# ESenseFE-PreAmpSingalInput.net
KiCad netlist of a schematic drawn in Altium Designer
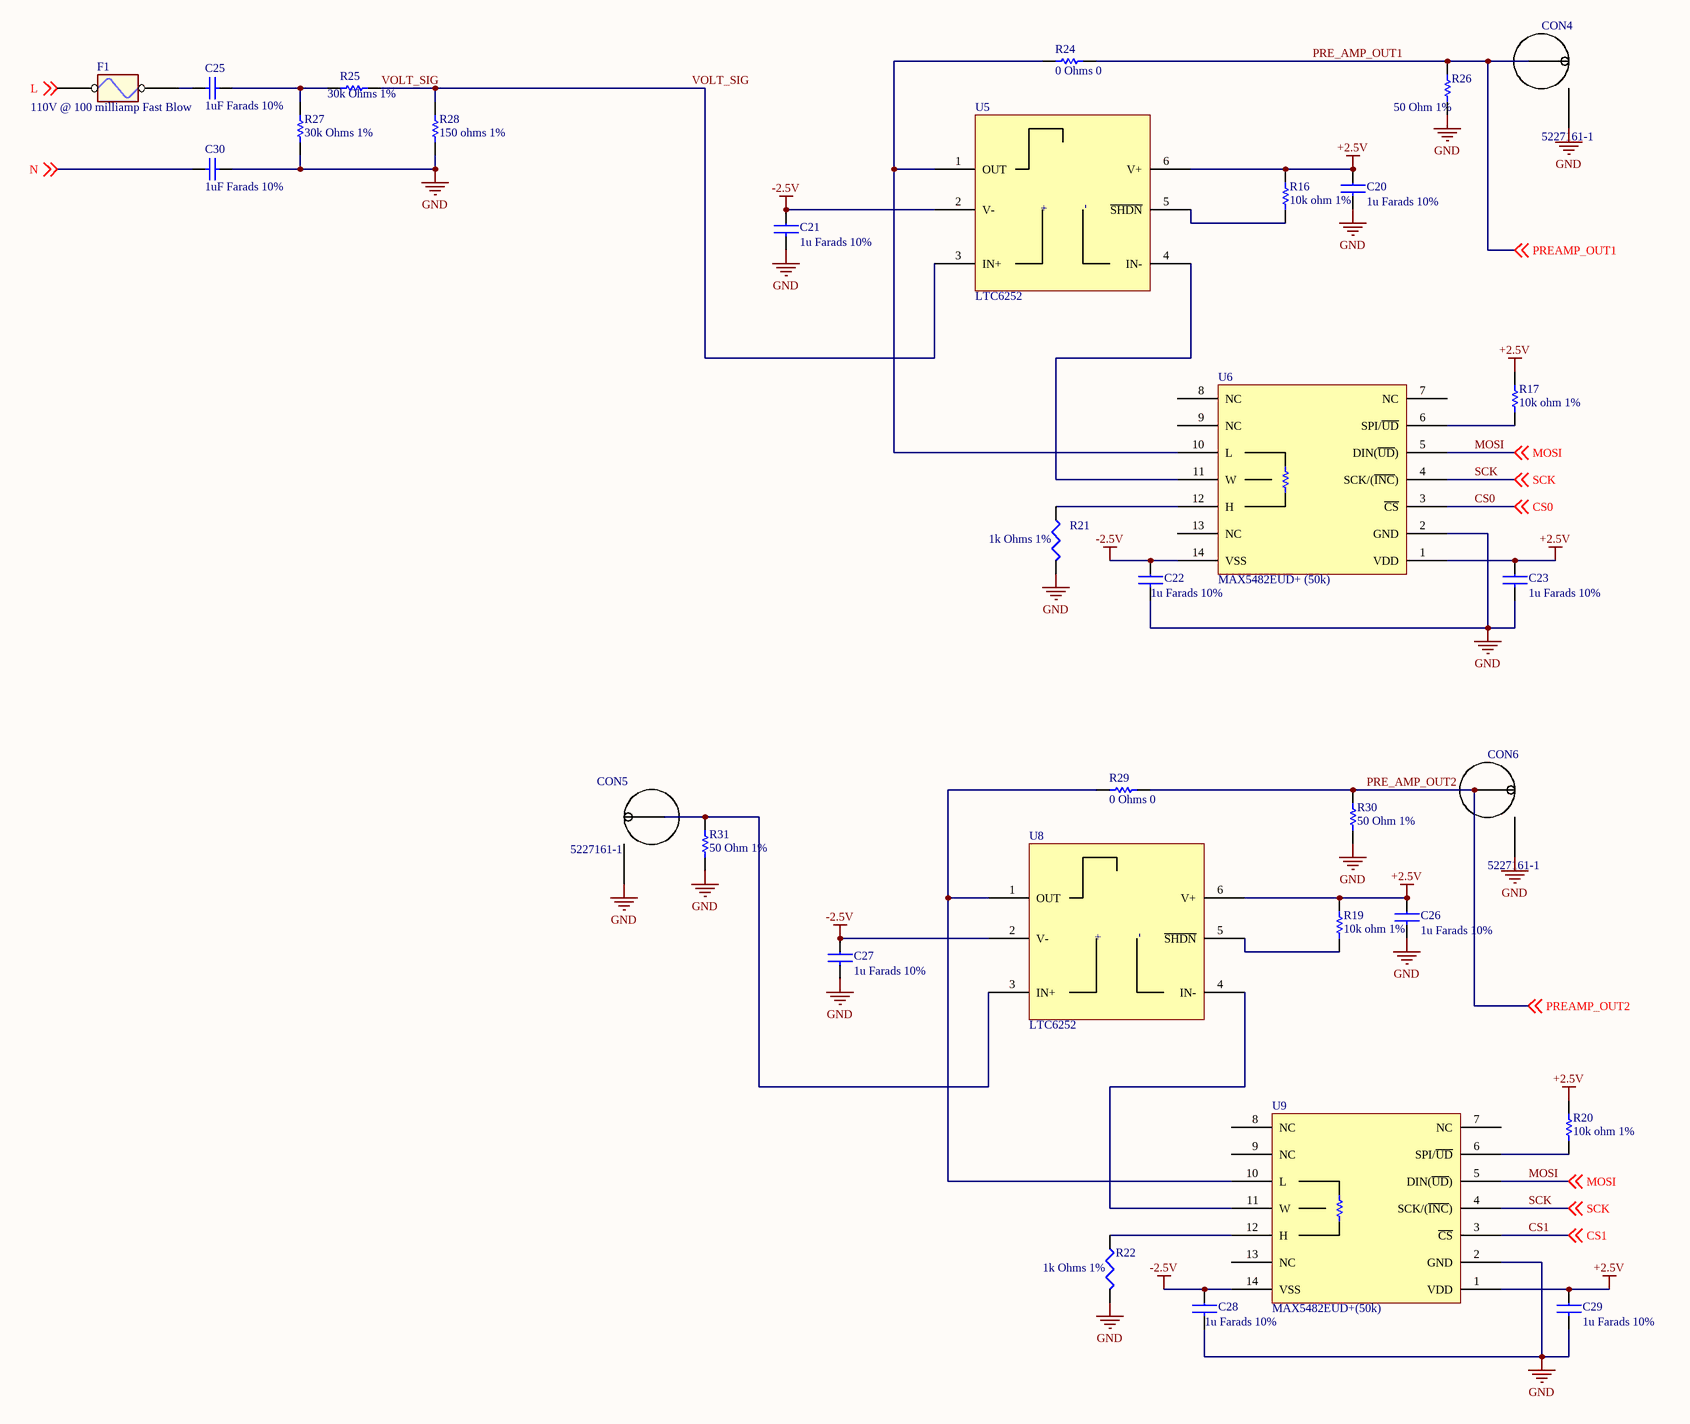
[diagram p0: ESenseFE-PreAmpSingalInput.SchDoc]

(export (version "E")
  (design (tool "Eeschema 10.0.6"))
  (components
    (comp (ref "C20")
      (value "1u Farads 10%")
      (footprint "SM/C_0603")
      (description "CAP CER 1.0UF 10V 10% X5R 0603")
      (fields (field (name "MFRPARTNUM") "GRM188R61A105KA61D"))
      (libsource (lib "FriedParts") (part "CAP NP"))
    )
    (comp (ref "C21")
      (value "1u Farads 10%")
      (footprint "SM/C_0603")
      (description "CAP CER 1.0UF 10V 10% X5R 0603")
      (fields (field (name "MFRPARTNUM") "GRM188R61A105KA61D"))
      (libsource (lib "FriedParts") (part "CAP NP"))
    )
    (comp (ref "C22")
      (value "1u Farads 10%")
      (footprint "SM/C_0603")
      (description "CAP CER 1.0UF 10V 10% X5R 0603")
      (fields (field (name "MFRPARTNUM") "GRM188R61A105KA61D"))
      (libsource (lib "FriedParts") (part "CAP NP"))
    )
    (comp (ref "C23")
      (value "1u Farads 10%")
      (footprint "SM/C_0603")
      (description "CAP CER 1.0UF 10V 10% X5R 0603")
      (fields (field (name "MFRPARTNUM") "GRM188R61A105KA61D"))
      (libsource (lib "FriedParts") (part "CAP NP"))
    )
    (comp (ref "C25")
      (value "1uF Farads 10%")
      (footprint "Y2-Caps-Epocs-1uF-10%")
      (description "Y2 Caps 1uF Epocs")
      (fields (field (name "MFRPARTNUM") "B32026B3105K"))
      (libsource (lib "FriedParts") (part "CAP"))
    )
    (comp (ref "C26")
      (value "1u Farads 10%")
      (footprint "SM/C_0603")
      (description "CAP CER 1.0UF 10V 10% X5R 0603")
      (fields (field (name "MFRPARTNUM") "GRM188R61A105KA61D"))
      (libsource (lib "FriedParts") (part "CAP NP"))
    )
    (comp (ref "C27")
      (value "1u Farads 10%")
      (footprint "SM/C_0603")
      (description "CAP CER 1.0UF 10V 10% X5R 0603")
      (fields (field (name "MFRPARTNUM") "GRM188R61A105KA61D"))
      (libsource (lib "FriedParts") (part "CAP NP"))
    )
    (comp (ref "C28")
      (value "1u Farads 10%")
      (footprint "SM/C_0603")
      (description "CAP CER 1.0UF 10V 10% X5R 0603")
      (fields (field (name "MFRPARTNUM") "GRM188R61A105KA61D"))
      (libsource (lib "FriedParts") (part "CAP NP"))
    )
    (comp (ref "C29")
      (value "1u Farads 10%")
      (footprint "SM/C_0603")
      (description "CAP CER 1.0UF 10V 10% X5R 0603")
      (fields (field (name "MFRPARTNUM") "GRM188R61A105KA61D"))
      (libsource (lib "FriedParts") (part "CAP NP"))
    )
    (comp (ref "C30")
      (value "1uF Farads 10%")
      (footprint "Y2-Caps-Epocs-1uF-10%")
      (description "Y2 Caps 1uF Epocs")
      (fields (field (name "MFRPARTNUM") "B32026B3105K"))
      (libsource (lib "FriedParts") (part "CAP"))
    )
    (comp (ref "CON4")
      (value "5227161-1")
      (footprint "BNC-RightAngle-PCB-50Ohm-Termination")
      (description "jack bnc, right angle, pcb; connector type:bnc, coaxial;")
      (libsource (lib "FriedParts") (part "BNC"))
    )
    (comp (ref "CON5")
      (value "5227161-1")
      (footprint "BNC-RightAngle-PCB-50Ohm-Termination")
      (description "jack bnc, right angle, pcb; connector type:bnc, coaxial;")
      (libsource (lib "FriedParts") (part "BNC"))
    )
    (comp (ref "CON6")
      (value "5227161-1")
      (footprint "BNC-RightAngle-PCB-50Ohm-Termination")
      (description "jack bnc, right angle, pcb; connector type:bnc, coaxial;")
      (libsource (lib "FriedParts") (part "BNC"))
    )
    (comp (ref "F1")
      (value "110V @ 100 milliamp Fast Blow")
      (footprint "WICKMANN/WK0011-ND")
      (description "FUSEHOLDER OPEN 5X20MM PC MNT")
      (fields (field (name "MFRPARTNUM") "6490000100"))
      (libsource (lib "FriedParts") (part "FUSEHOLDER"))
    )
    (comp (ref "R16")
      (value "10k ohm 1%")
      (footprint "SM/C_0603")
      (description "resistor, 0603, 0.1w, 1%, 10k; resistance:10kohm; resistance")
      (fields (field (name "MFRPARTNUM") "ERJ-3EKF1002V") (field (name "PUBLISHER") "Altium Limited"))
      (libsource (lib "FriedParts") (part "Res1"))
    )
    (comp (ref "R17")
      (value "10k ohm 1%")
      (footprint "SM/C_0603")
      (description "resistor, 0603, 0.1w, 1%, 10k; resistance:10kohm; resistance")
      (fields (field (name "MFRPARTNUM") "ERJ-3EKF1002V") (field (name "PUBLISHER") "Altium Limited"))
      (libsource (lib "FriedParts") (part "Res1"))
    )
    (comp (ref "R19")
      (value "10k ohm 1%")
      (footprint "SM/C_0603")
      (description "resistor, 0603, 0.1w, 1%, 10k; resistance:10kohm; resistance")
      (fields (field (name "MFRPARTNUM") "ERJ-3EKF1002V") (field (name "PUBLISHER") "Altium Limited"))
      (libsource (lib "FriedParts") (part "Res1"))
    )
    (comp (ref "R20")
      (value "10k ohm 1%")
      (footprint "SM/C_0603")
      (description "resistor, 0603, 0.1w, 1%, 10k; resistance:10kohm; resistance")
      (fields (field (name "MFRPARTNUM") "ERJ-3EKF1002V") (field (name "PUBLISHER") "Altium Limited"))
      (libsource (lib "FriedParts") (part "Res1"))
    )
    (comp (ref "R21")
      (value "1k Ohms 1%")
      (footprint "SM/C_0603")
      (description "RES 1.00K OHM 1/10W 1% 0603 SMD")
      (fields (field (name "MFRPARTNUM") "ERJ-3EKF1001V"))
      (libsource (lib "FriedParts") (part "R"))
    )
    (comp (ref "R22")
      (value "1k Ohms 1%")
      (footprint "SM/C_0603")
      (description "RES 1.00K OHM 1/10W 1% 0603 SMD")
      (fields (field (name "MFRPARTNUM") "ERJ-3EKF1001V"))
      (libsource (lib "FriedParts") (part "R"))
    )
    (comp (ref "R24")
      (value "0 Ohms 0")
      (footprint "SM/R_0603")
      (description "res thick film 0603 0 ohm 1/10w molded smd punched carrier")
      (fields (field (name "MFRPARTNUM") "ERJ-3GEY0R00V") (field (name "PUBLISHER") "Altium Limited"))
      (libsource (lib "FriedParts") (part "Res1"))
    )
    (comp (ref "R25")
      (value "30k Ohms 1%")
      (footprint "SM/R_2512")
      (description "single components passive components resistors")
      (fields (field (name "MFRPARTNUM") "ERJ-1TNF3002U") (field (name "PUBLISHER") "Altium Limited"))
      (libsource (lib "FriedParts") (part "Res1"))
    )
    (comp (ref "R26")
      (value "50 Ohm 1%")
      (footprint "SM/R_0603")
      (description "; resistance:50ohm; resistance tolerance:± 0.1%; power")
      (fields (field (name "MFRPARTNUM") "FC0603E50R0BTBST1") (field (name "PUBLISHER") "Altium Limited"))
      (libsource (lib "FriedParts") (part "Res1"))
    )
    (comp (ref "R27")
      (value "30k Ohms 1%")
      (footprint "SM/R_2512")
      (description "single components passive components resistors")
      (fields (field (name "MFRPARTNUM") "ERJ-1TNF3002U") (field (name "PUBLISHER") "Altium Limited"))
      (libsource (lib "FriedParts") (part "Res1"))
    )
    (comp (ref "R28")
      (value "150 ohms 1%")
      (footprint "SM/R_2512")
      (description "single components passive components resistors")
      (fields (field (name "MFRPARTNUM") "ERJ-1TNF15R0U") (field (name "PUBLISHER") "Altium Limited"))
      (libsource (lib "FriedParts") (part "Res1"))
    )
    (comp (ref "R29")
      (value "0 Ohms 0")
      (footprint "SM/R_0603")
      (description "res thick film 0603 0 ohm 1/10w molded smd punched carrier")
      (fields (field (name "MFRPARTNUM") "ERJ-3GEY0R00V") (field (name "PUBLISHER") "Altium Limited"))
      (libsource (lib "FriedParts") (part "Res1"))
    )
    (comp (ref "R30")
      (value "50 Ohm 1%")
      (footprint "SM/R_0603")
      (description "; resistance:50ohm; resistance tolerance:± 0.1%; power")
      (fields (field (name "MFRPARTNUM") "FC0603E50R0BTBST1") (field (name "PUBLISHER") "Altium Limited"))
      (libsource (lib "FriedParts") (part "Res1"))
    )
    (comp (ref "R31")
      (value "50 Ohm 1%")
      (footprint "SM/R_0603")
      (description "; resistance:50ohm; resistance tolerance:± 0.1%; power")
      (fields (field (name "MFRPARTNUM") "FC0603E50R0BTBST1") (field (name "PUBLISHER") "Altium Limited"))
      (libsource (lib "FriedParts") (part "Res1"))
    )
    (comp (ref "U5")
      (value "LTC6252")
      (footprint "TSOT-23-LTC6252-OpAmp")
      (description "op amp, r/r 200mhz single, soic8; no. of amplifiers:1; op amp")
      (libsource (lib "FriedParts") (part "LTC6252"))
    )
    (comp (ref "U6")
      (value "MAX5482EUD+ (50k)")
      (footprint "TSSOP-16Lead-MAX548X")
      (description "dpot, nv, linear taper, 10 bit, smd; resistance range")
      (fields (field (name "MFRPARTNUM") "MAX5482EUD+(1)"))
      (libsource (lib "FriedParts") (part "MAX5482"))
    )
    (comp (ref "U8")
      (value "LTC6252")
      (footprint "TSOT-23-LTC6252-OpAmp")
      (description "op amp, r/r 200mhz single, soic8; no. of amplifiers:1; op amp")
      (libsource (lib "FriedParts") (part "LTC6252"))
    )
    (comp (ref "U9")
      (value "MAX5482EUD+(50k)")
      (footprint "TSSOP-16Lead-MAX548X")
      (description "dpot, nv, linear taper, 10 bit, smd; resistance range")
      (fields (field (name "MFRPARTNUM") "MAX5482EUD+(1)"))
      (libsource (lib "FriedParts") (part "MAX5482"))
    )
  )
  (nets
    (net (code "1") (name "+2.5V") (class "Default")
      (node (ref "C20") (pin "1") (pinfunction "1_1") (pintype "passive"))
      (node (ref "C23") (pin "1") (pinfunction "1_1") (pintype "passive"))
      (node (ref "C26") (pin "1") (pinfunction "1_1") (pintype "passive"))
      (node (ref "C29") (pin "1") (pinfunction "1_1") (pintype "passive"))
      (node (ref "R16") (pin "2") (pinfunction "2_2") (pintype "passive"))
      (node (ref "R17") (pin "2") (pinfunction "2_2") (pintype "passive"))
      (node (ref "R19") (pin "2") (pinfunction "2_2") (pintype "passive"))
      (node (ref "R20") (pin "2") (pinfunction "2_2") (pintype "passive"))
      (node (ref "U5") (pin "6") (pinfunction "V+_6") (pintype "passive"))
      (node (ref "U6") (pin "1") (pinfunction "VDD_1") (pintype "passive"))
      (node (ref "U8") (pin "6") (pinfunction "V+_6") (pintype "passive"))
      (node (ref "U9") (pin "1") (pinfunction "VDD_1") (pintype "passive"))
    )
    (net (code "2") (name "-2.5V") (class "Default")
      (node (ref "C21") (pin "1") (pinfunction "1_1") (pintype "passive"))
      (node (ref "C22") (pin "1") (pinfunction "1_1") (pintype "passive"))
      (node (ref "C27") (pin "1") (pinfunction "1_1") (pintype "passive"))
      (node (ref "C28") (pin "1") (pinfunction "1_1") (pintype "passive"))
      (node (ref "U5") (pin "2") (pinfunction "V-_2") (pintype "passive"))
      (node (ref "U6") (pin "14") (pinfunction "VSS_14") (pintype "passive"))
      (node (ref "U8") (pin "2") (pinfunction "V-_2") (pintype "passive"))
      (node (ref "U9") (pin "14") (pinfunction "VSS_14") (pintype "passive"))
    )
    (net (code "3") (name "/VOLT_SIG") (class "Default")
      (node (ref "R25") (pin "1") (pinfunction "1_1") (pintype "passive"))
      (node (ref "R28") (pin "2") (pinfunction "2_2") (pintype "passive"))
      (node (ref "U5") (pin "3") (pinfunction "IN+_3") (pintype "passive"))
    )
    (net (code "4") (name "CS0") (class "Default")
      (node (ref "U6") (pin "3") (pinfunction "~{CS}_3") (pintype "passive"))
    )
    (net (code "5") (name "CS1") (class "Default")
      (node (ref "U9") (pin "3") (pinfunction "~{CS}_3") (pintype "passive"))
    )
    (net (code "6") (name "GND") (class "Default")
      (node (ref "C20") (pin "2") (pinfunction "2_2") (pintype "passive"))
      (node (ref "C21") (pin "2") (pinfunction "2_2") (pintype "passive"))
      (node (ref "C22") (pin "2") (pinfunction "2_2") (pintype "passive"))
      (node (ref "C23") (pin "2") (pinfunction "2_2") (pintype "passive"))
      (node (ref "C26") (pin "2") (pinfunction "2_2") (pintype "passive"))
      (node (ref "C27") (pin "2") (pinfunction "2_2") (pintype "passive"))
      (node (ref "C28") (pin "2") (pinfunction "2_2") (pintype "passive"))
      (node (ref "C29") (pin "2") (pinfunction "2_2") (pintype "passive"))
      (node (ref "C30") (pin "2") (pinfunction "2_2") (pintype "passive"))
      (node (ref "CON4") (pin "2") (pinfunction "2_2") (pintype "passive"))
      (node (ref "CON5") (pin "2") (pinfunction "2_2") (pintype "passive"))
      (node (ref "CON6") (pin "2") (pinfunction "2_2") (pintype "passive"))
      (node (ref "R21") (pin "2") (pinfunction "2_2") (pintype "passive"))
      (node (ref "R22") (pin "2") (pinfunction "2_2") (pintype "passive"))
      (node (ref "R26") (pin "1") (pinfunction "1_1") (pintype "passive"))
      (node (ref "R27") (pin "1") (pinfunction "1_1") (pintype "passive"))
      (node (ref "R28") (pin "1") (pinfunction "1_1") (pintype "passive"))
      (node (ref "R30") (pin "1") (pinfunction "1_1") (pintype "passive"))
      (node (ref "R31") (pin "1") (pinfunction "1_1") (pintype "passive"))
      (node (ref "U6") (pin "2") (pinfunction "GND_2") (pintype "passive"))
      (node (ref "U9") (pin "2") (pinfunction "GND_2") (pintype "passive"))
    )
    (net (code "7") (name "L") (class "Default")
      (node (ref "F1") (pin "1") (pinfunction "1_1") (pintype "passive"))
    )
    (net (code "8") (name "MOSI") (class "Default")
      (node (ref "U6") (pin "5") (pinfunction "DIN(~{UD})_5") (pintype "passive"))
      (node (ref "U9") (pin "5") (pinfunction "DIN(~{UD})_5") (pintype "passive"))
    )
    (net (code "9") (name "N") (class "Default")
      (node (ref "C30") (pin "1") (pinfunction "1_1") (pintype "passive"))
    )
    (net (code "10") (name "Net-(C25-Pad1)") (class "Default")
      (node (ref "C25") (pin "1") (pinfunction "1_1") (pintype "passive"))
      (node (ref "F1") (pin "2") (pinfunction "2_2") (pintype "passive"))
    )
    (net (code "11") (name "Net-(C25-Pad2)") (class "Default")
      (node (ref "C25") (pin "2") (pinfunction "2_2") (pintype "passive"))
      (node (ref "R25") (pin "2") (pinfunction "2_2") (pintype "passive"))
      (node (ref "R27") (pin "2") (pinfunction "2_2") (pintype "passive"))
    )
    (net (code "12") (name "Net-(U5-IN-)") (class "Default")
      (node (ref "U5") (pin "4") (pinfunction "IN-_4") (pintype "passive"))
      (node (ref "U6") (pin "11") (pinfunction "W_11") (pintype "passive"))
    )
    (net (code "13") (name "Net-(U5-OUT)") (class "Default")
      (node (ref "R24") (pin "1") (pinfunction "1_1") (pintype "passive"))
      (node (ref "U5") (pin "1") (pinfunction "OUT_1") (pintype "passive"))
      (node (ref "U6") (pin "10") (pinfunction "L_10") (pintype "passive"))
    )
    (net (code "14") (name "Net-(U5-~{SHDN})") (class "Default")
      (node (ref "R16") (pin "1") (pinfunction "1_1") (pintype "passive"))
      (node (ref "U5") (pin "5") (pinfunction "~{SHDN}_5") (pintype "passive"))
    )
    (net (code "15") (name "Net-(U6-H)") (class "Default")
      (node (ref "R21") (pin "1") (pinfunction "1_1") (pintype "passive"))
      (node (ref "U6") (pin "12") (pinfunction "H_12") (pintype "passive"))
    )
    (net (code "16") (name "Net-(U6-SPI{slash}~{UD})") (class "Default")
      (node (ref "R17") (pin "1") (pinfunction "1_1") (pintype "passive"))
      (node (ref "U6") (pin "6") (pinfunction "SPI/~{UD}_6") (pintype "passive"))
    )
    (net (code "17") (name "Net-(U8-IN+)") (class "Default")
      (node (ref "CON5") (pin "1") (pinfunction "1_1") (pintype "passive"))
      (node (ref "R31") (pin "2") (pinfunction "2_2") (pintype "passive"))
      (node (ref "U8") (pin "3") (pinfunction "IN+_3") (pintype "passive"))
    )
    (net (code "18") (name "Net-(U8-IN-)") (class "Default")
      (node (ref "U8") (pin "4") (pinfunction "IN-_4") (pintype "passive"))
      (node (ref "U9") (pin "11") (pinfunction "W_11") (pintype "passive"))
    )
    (net (code "19") (name "Net-(U8-OUT)") (class "Default")
      (node (ref "R29") (pin "1") (pinfunction "1_1") (pintype "passive"))
      (node (ref "U8") (pin "1") (pinfunction "OUT_1") (pintype "passive"))
      (node (ref "U9") (pin "10") (pinfunction "L_10") (pintype "passive"))
    )
    (net (code "20") (name "Net-(U8-~{SHDN})") (class "Default")
      (node (ref "R19") (pin "1") (pinfunction "1_1") (pintype "passive"))
      (node (ref "U8") (pin "5") (pinfunction "~{SHDN}_5") (pintype "passive"))
    )
    (net (code "21") (name "Net-(U9-H)") (class "Default")
      (node (ref "R22") (pin "1") (pinfunction "1_1") (pintype "passive"))
      (node (ref "U9") (pin "12") (pinfunction "H_12") (pintype "passive"))
    )
    (net (code "22") (name "Net-(U9-SPI{slash}~{UD})") (class "Default")
      (node (ref "R20") (pin "1") (pinfunction "1_1") (pintype "passive"))
      (node (ref "U9") (pin "6") (pinfunction "SPI/~{UD}_6") (pintype "passive"))
    )
    (net (code "23") (name "PREAMP_OUT1") (class "Default")
      (node (ref "CON4") (pin "1") (pinfunction "1_1") (pintype "passive"))
      (node (ref "R24") (pin "2") (pinfunction "2_2") (pintype "passive"))
      (node (ref "R26") (pin "2") (pinfunction "2_2") (pintype "passive"))
    )
    (net (code "24") (name "PREAMP_OUT2") (class "Default")
      (node (ref "CON6") (pin "1") (pinfunction "1_1") (pintype "passive"))
      (node (ref "R29") (pin "2") (pinfunction "2_2") (pintype "passive"))
      (node (ref "R30") (pin "2") (pinfunction "2_2") (pintype "passive"))
    )
    (net (code "25") (name "SCK") (class "Default")
      (node (ref "U6") (pin "4") (pinfunction "SCK/(~{INC})_4") (pintype "passive"))
      (node (ref "U9") (pin "4") (pinfunction "SCK/(~{INC})_4") (pintype "passive"))
    )
    (net (code "26") (name "unconnected-(U6-NC-Pad7)") (class "Default")
      (node (ref "U6") (pin "7") (pinfunction "NC_7") (pintype "passive"))
    )
    (net (code "27") (name "unconnected-(U6-NC-Pad8)") (class "Default")
      (node (ref "U6") (pin "8") (pinfunction "NC_8") (pintype "passive"))
    )
    (net (code "28") (name "unconnected-(U6-NC-Pad9)") (class "Default")
      (node (ref "U6") (pin "9") (pinfunction "NC_9") (pintype "passive"))
    )
    (net (code "29") (name "unconnected-(U6-NC-Pad13)") (class "Default")
      (node (ref "U6") (pin "13") (pinfunction "NC_13") (pintype "passive"))
    )
    (net (code "30") (name "unconnected-(U9-NC-Pad7)") (class "Default")
      (node (ref "U9") (pin "7") (pinfunction "NC_7") (pintype "passive"))
    )
    (net (code "31") (name "unconnected-(U9-NC-Pad8)") (class "Default")
      (node (ref "U9") (pin "8") (pinfunction "NC_8") (pintype "passive"))
    )
    (net (code "32") (name "unconnected-(U9-NC-Pad9)") (class "Default")
      (node (ref "U9") (pin "9") (pinfunction "NC_9") (pintype "passive"))
    )
    (net (code "33") (name "unconnected-(U9-NC-Pad13)") (class "Default")
      (node (ref "U9") (pin "13") (pinfunction "NC_13") (pintype "passive"))
    )
  )
)
